# stm32_1.net
KiCad netlist of a schematic drawn in EasyEDA
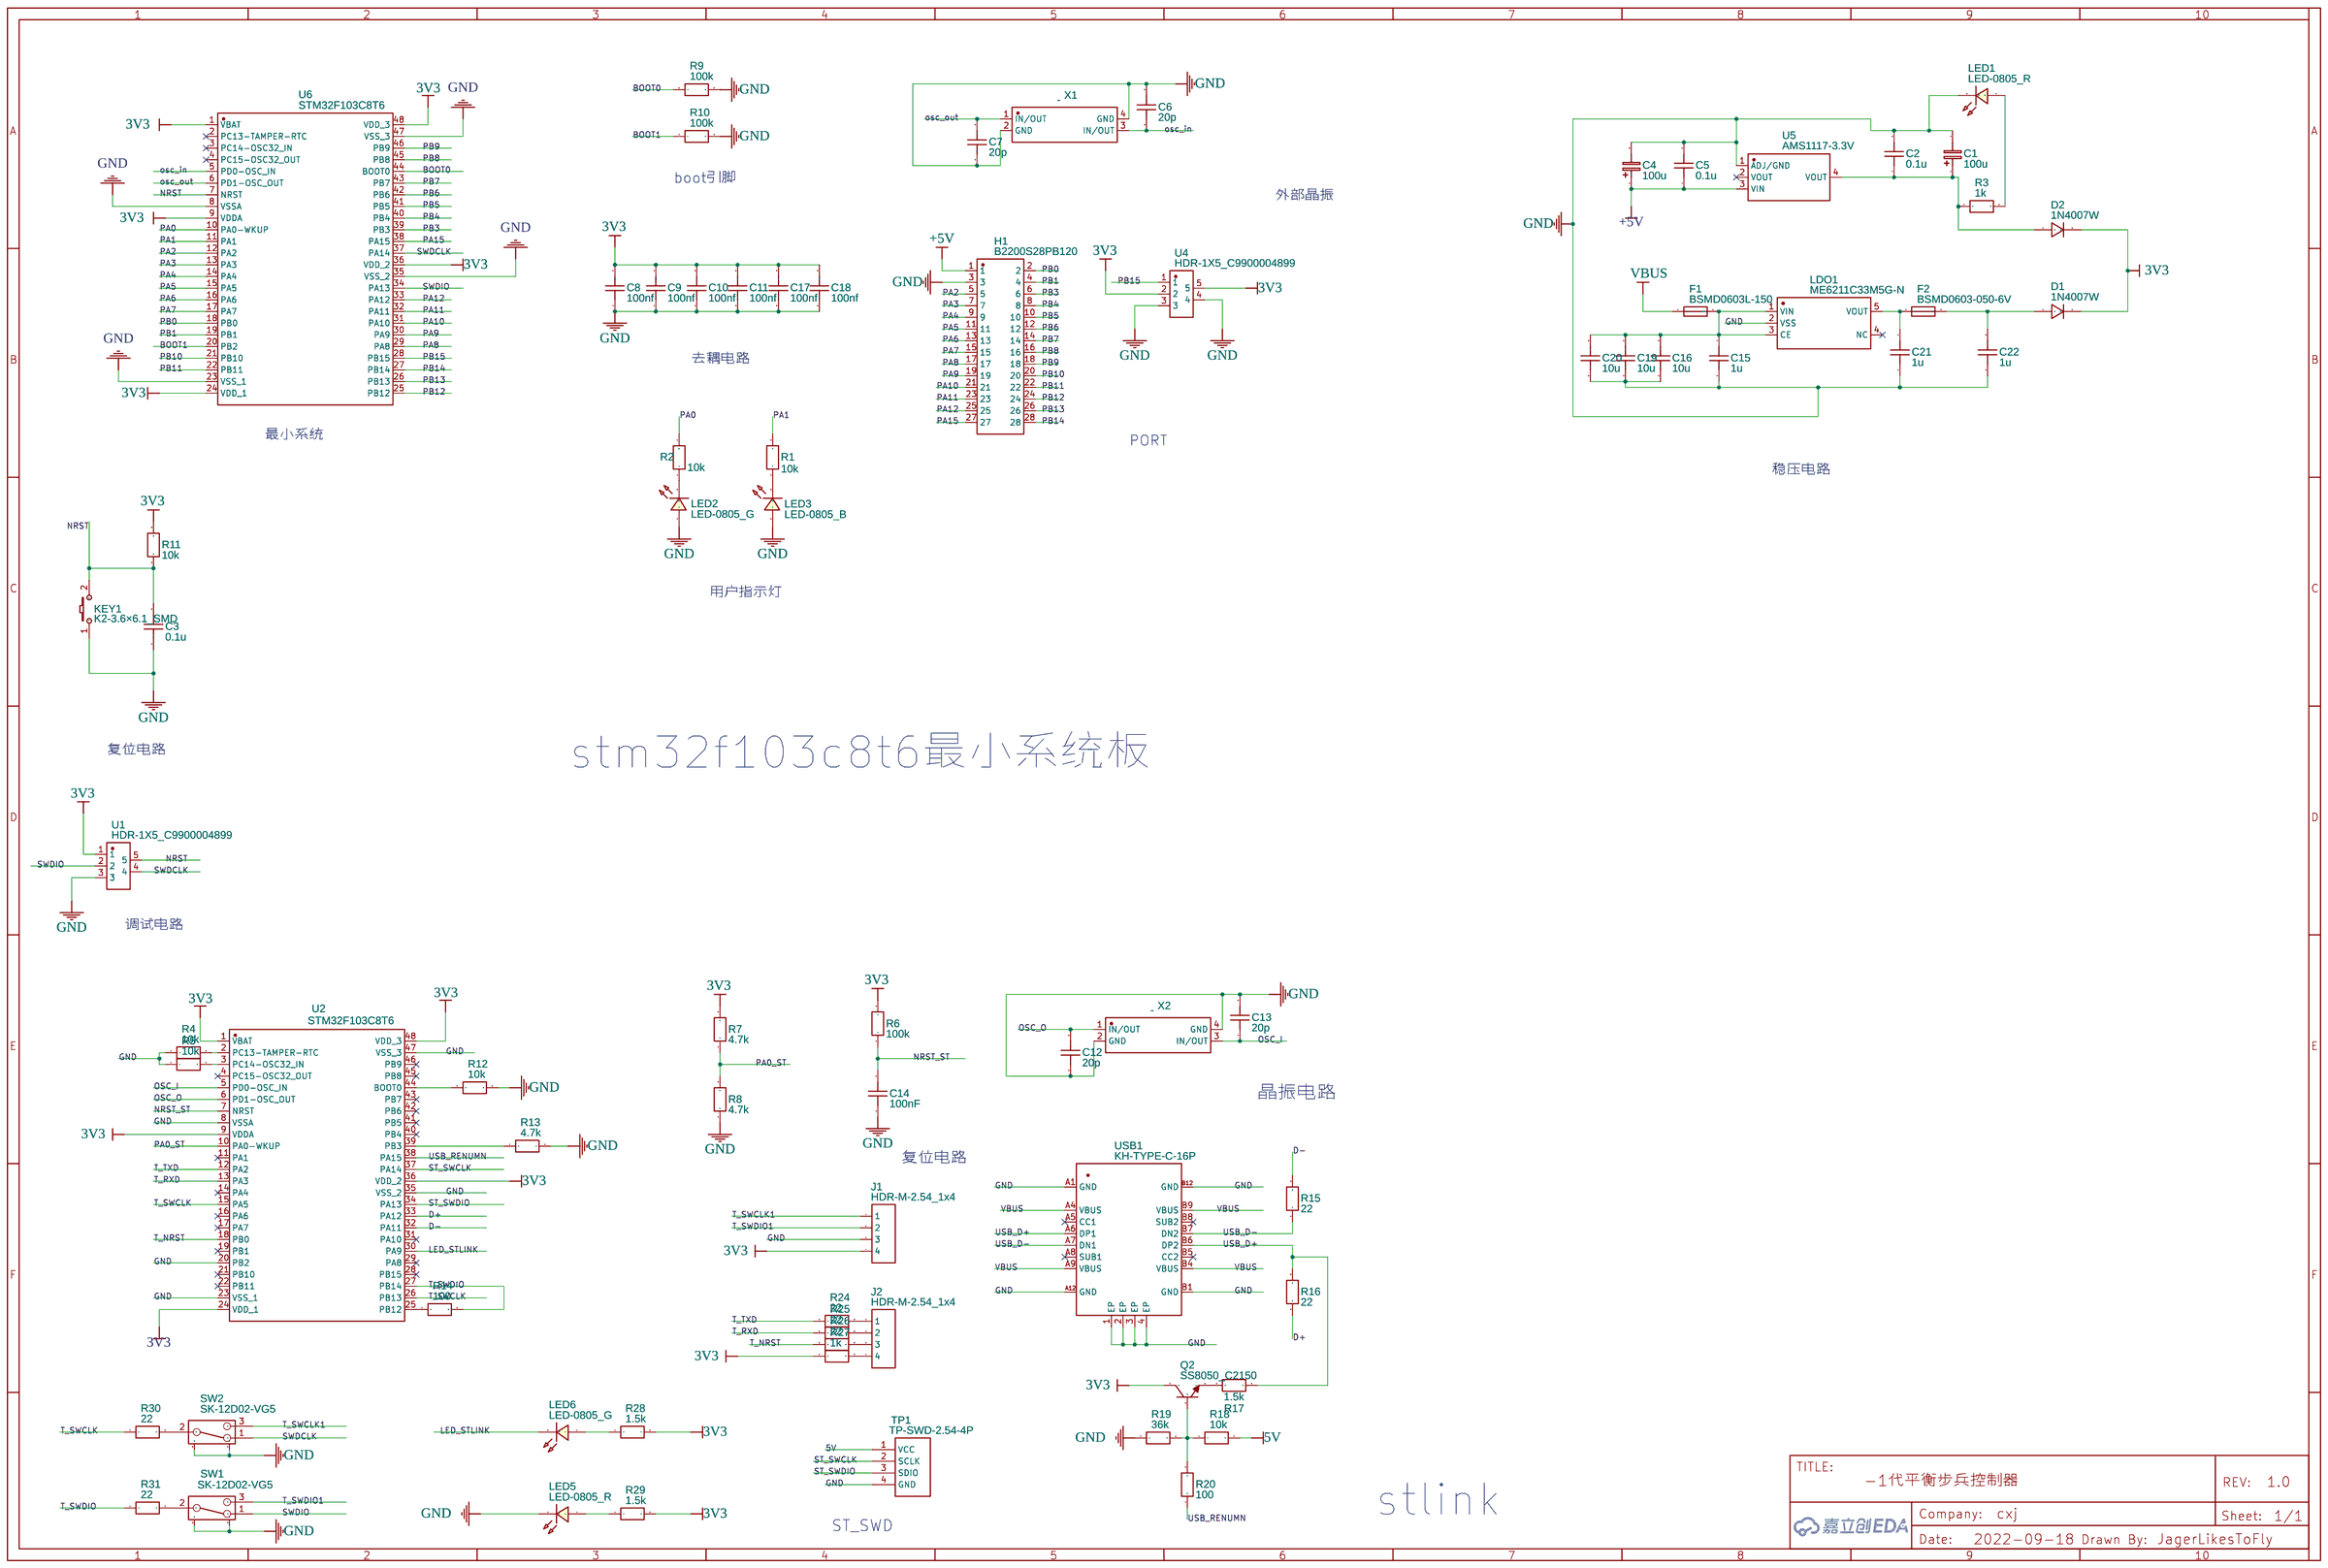
[diagram p0: schematic sheet]

(export (version "E")
  (design (tool "Eeschema 10.0.6"))
  (components
    (comp (ref "C1") (value "100u") (libsource (lib "") (part "C_Tan_SMD_A_EU")))
    (comp (ref "C2") (value "0.1u") (libsource (lib "") (part "C_0805_US")))
    (comp (ref "C3") (value "0.1u") (libsource (lib "") (part "C_0603_US")))
    (comp (ref "C4") (value "100u") (libsource (lib "") (part "C_Tan_SMD_A_EU")))
    (comp (ref "C5") (value "0.1u") (libsource (lib "") (part "C_0805_US")))
    (comp (ref "C6") (value "20p") (libsource (lib "") (part "C_0805_US")))
    (comp (ref "C7") (value "20p") (libsource (lib "") (part "C_0805_US")))
    (comp (ref "C8") (value "100nf") (libsource (lib "") (part "C_0603_US")))
    (comp (ref "C9") (value "100nf") (libsource (lib "") (part "C_0603_US")))
    (comp (ref "C10") (value "100nf") (libsource (lib "") (part "C_0603_US")))
    (comp (ref "C11") (value "100nf") (libsource (lib "") (part "C_0603_US")))
    (comp (ref "C12") (value "20p") (libsource (lib "") (part "C_0805_US")))
    (comp (ref "C13") (value "20p") (libsource (lib "") (part "C_0805_US")))
    (comp (ref "C14") (value "100nF") (libsource (lib "") (part "C_0805_US")))
    (comp (ref "C15") (value "1u") (libsource (lib "") (part "C_0805_US_1")))
    (comp (ref "C16") (value "10u") (libsource (lib "") (part "C_0805_US")))
    (comp (ref "C17") (value "100nf") (libsource (lib "") (part "C_0603_US")))
    (comp (ref "C18") (value "100nf") (libsource (lib "") (part "C_0603_US")))
    (comp (ref "C19") (value "10u") (libsource (lib "") (part "C_0805_US")))
    (comp (ref "C20") (value "10u") (libsource (lib "") (part "C_0805_US")))
    (comp (ref "C21") (value "1u") (libsource (lib "") (part "C_0805_US")))
    (comp (ref "C22") (value "1u") (libsource (lib "") (part "C_0805_US")))
    (comp (ref "D1")
      (value "1N4007W")
      (fields (field (name "BOM_Supplier Part") "C328592"))
      (libsource (lib "") (part "1N4007W"))
    )
    (comp (ref "D2")
      (value "1N4007W")
      (fields (field (name "BOM_Supplier Part") "C328592"))
      (libsource (lib "") (part "1N4007W"))
    )
    (comp (ref "F1")
      (value "BSMD0603L-150")
      (fields (field (name "BOM_Supplier Part") "C914094"))
      (libsource (lib "") (part "BSMD0603L-150"))
    )
    (comp (ref "F2")
      (value "BSMD0603-050-6V")
      (fields (field (name "BOM_Supplier Part") "C883095"))
      (libsource (lib "") (part "BSMD0603-050-6V"))
    )
    (comp (ref "H1")
      (value "B2200S28PB120")
      (fields (field (name "BOM_Supplier Part") "C379815"))
      (libsource (lib "") (part "B2200S28PB120"))
    )
    (comp (ref "J1")
      (value "HDR-M-2.54_1x4")
      (fields (field (name "BOM_Supplier Part") "C124378"))
      (libsource (lib "") (part "HDR-M-2.54_1x4"))
    )
    (comp (ref "J2")
      (value "HDR-M-2.54_1x4")
      (fields (field (name "BOM_Supplier Part") "C124378"))
      (libsource (lib "") (part "HDR-M-2.54_1x4"))
    )
    (comp (ref "KEY1")
      (value "K2-3.6×6.1_SMD")
      (fields
        (field (name "BOM_Manufacturer Part") "K2-1107ST-A4SW-06")
        (field (name "BOM_Supplier Part") "C118141")
      )
      (libsource (lib "") (part "K2-3.6×6.1_SMD"))
    )
    (comp (ref "LDO1")
      (value "ME6211C33M5G-N")
      (fields (field (name "BOM_Supplier Part") "C82942"))
      (libsource (lib "") (part "ME6211C33M5G-N"))
    )
    (comp (ref "LED1")
      (value "LED-0805_R")
      (fields
        (field (name "BOM_Manufacturer Part") "19-217/R6C-AL1M2VY/3T")
        (field (name "BOM_Supplier Part") "C72044")
      )
      (libsource (lib "") (part "LED-0603_R"))
    )
    (comp (ref "LED2")
      (value "LED-0805_G")
      (fields (field (name "BOM_Manufacturer Part") "NCD0805G1") (field (name "BOM_Supplier Part") "C84260"))
      (libsource (lib "") (part "LED-0805_G"))
    )
    (comp (ref "LED3")
      (value "LED-0805_B")
      (fields
        (field (name "BOM_Manufacturer Part") "D-B080508B1-KS2")
        (field (name "BOM_Supplier Part") "C108412")
      )
      (libsource (lib "") (part "LED-0805_B"))
    )
    (comp (ref "LED5")
      (value "LED-0805_R")
      (fields
        (field (name "BOM_Manufacturer Part") "17-21SURC/S530-A3/TR8")
        (field (name "BOM_Supplier Part") "C72037")
      )
      (libsource (lib "") (part "LED-0805_R"))
    )
    (comp (ref "LED6")
      (value "LED-0805_G")
      (fields (field (name "BOM_Manufacturer Part") "NCD0805G1") (field (name "BOM_Supplier Part") "C84260"))
      (libsource (lib "") (part "LED-0805_G_1"))
    )
    (comp (ref "Q2")
      (value "SS8050_C2150")
      (fields (field (name "BOM_Manufacturer Part") "SS8050") (field (name "BOM_Supplier Part") "C2150"))
      (libsource (lib "") (part "SS8050_C2150"))
    )
    (comp (ref "R1") (value "10k") (libsource (lib "") (part "R_0805_EU_1")))
    (comp (ref "R2") (value "10k") (libsource (lib "") (part "R_0805_EU_1")))
    (comp (ref "R3") (value "1k") (libsource (lib "") (part "R_0805_EU")))
    (comp (ref "R4") (value "10k") (libsource (lib "") (part "R_0805_EU")))
    (comp (ref "R5") (value "10k") (libsource (lib "") (part "R_0805_EU")))
    (comp (ref "R6") (value "100k") (libsource (lib "") (part "R_0805_EU_1")))
    (comp (ref "R7") (value "4.7k") (libsource (lib "") (part "R_0805_EU_1")))
    (comp (ref "R8") (value "4.7k") (libsource (lib "") (part "R_0805_EU_1")))
    (comp (ref "R9") (value "100k") (libsource (lib "") (part "R_0603_EU_1")))
    (comp (ref "R10") (value "100k") (libsource (lib "") (part "R_0603_EU_1")))
    (comp (ref "R11") (value "10k") (libsource (lib "") (part "R_0603_EU")))
    (comp (ref "R12") (value "10k") (libsource (lib "") (part "R_0805_EU")))
    (comp (ref "R13") (value "4.7k") (libsource (lib "") (part "R_0805_EU")))
    (comp (ref "R14") (value "100") (libsource (lib "") (part "R_0805_EU")))
    (comp (ref "R15") (value "22") (libsource (lib "") (part "R_0805_EU_1")))
    (comp (ref "R16") (value "22") (libsource (lib "") (part "R_0805_EU_1")))
    (comp (ref "R17") (value "1.5k") (libsource (lib "") (part "R_0805_EU")))
    (comp (ref "R18") (value "10k") (libsource (lib "") (part "R_0805_EU")))
    (comp (ref "R19") (value "36k") (libsource (lib "") (part "R_0805_EU")))
    (comp (ref "R20") (value "100") (libsource (lib "") (part "R_0805_EU_1")))
    (comp (ref "R24") (value "22") (libsource (lib "") (part "R_0805_EU")))
    (comp (ref "R25") (value "22") (libsource (lib "") (part "R_0805_EU")))
    (comp (ref "R26") (value "22") (libsource (lib "") (part "R_0805_EU")))
    (comp (ref "R27") (value "1k") (libsource (lib "") (part "R_0805_EU")))
    (comp (ref "R28") (value "1.5k") (libsource (lib "") (part "R_0805_EU")))
    (comp (ref "R29") (value "1.5k") (libsource (lib "") (part "R_0805_EU")))
    (comp (ref "R30") (value "22") (libsource (lib "") (part "R_0805_EU")))
    (comp (ref "R31") (value "22") (libsource (lib "") (part "R_0805_EU")))
    (comp (ref "SW1")
      (value "SK-12D02-VG5")
      (fields (field (name "BOM_Supplier Part") "C136722"))
      (libsource (lib "") (part "SK-12D02-VG5"))
    )
    (comp (ref "SW2")
      (value "SK-12D02-VG5")
      (fields (field (name "BOM_Supplier Part") "C136722"))
      (libsource (lib "") (part "SK-12D02-VG5"))
    )
    (comp (ref "TP1") (value "TP-SWD-2.54-4P") (libsource (lib "") (part "TP-SWD-2.54-4P")))
    (comp (ref "U1")
      (value "HDR-1X5_C9900004899")
      (fields
        (field (name "BOM_Manufacturer Part") "HDR-1X5")
        (field (name "BOM_Supplier Part") "C9900004899")
      )
      (libsource (lib "") (part "HDR-1X5_C9900004899"))
    )
    (comp (ref "U2")
      (value "STM32F103C8T6")
      (fields (field (name "BOM_Supplier Part") "C8734"))
      (libsource (lib "") (part "STM32F103C8T6"))
    )
    (comp (ref "U4")
      (value "HDR-1X5_C9900004899")
      (fields
        (field (name "BOM_Manufacturer Part") "HDR-1X5")
        (field (name "BOM_Supplier Part") "C9900004899")
      )
      (libsource (lib "") (part "HDR-1X5_C9900004899"))
    )
    (comp (ref "U5")
      (value "AMS1117-3.3V")
      (fields (field (name "BOM_Supplier Part") "C2688239"))
      (libsource (lib "") (part "AMS1117-3.3V"))
    )
    (comp (ref "U6")
      (value "STM32F103C8T6")
      (fields (field (name "BOM_Supplier Part") "C8734"))
      (libsource (lib "") (part "STM32F103C8T6"))
    )
    (comp (ref "USB1")
      (value "KH-TYPE-C-16P")
      (fields (field (name "BOM_Supplier Part") "C709357"))
      (libsource (lib "") (part "KH-TYPE-C-16P"))
    )
    (comp (ref "X1")
      (value "-")
      (fields (field (name "BOM_Manufacturer Part") "TZ1897B") (field (name "BOM_Supplier Part") "C337647"))
      (libsource (lib "") (part "TZ1897B"))
    )
    (comp (ref "X2")
      (value "-")
      (fields (field (name "BOM_Manufacturer Part") "TZ1897B") (field (name "BOM_Supplier Part") "C337647"))
      (libsource (lib "") (part "TZ1897B"))
    )
  )
  (nets
    (net (code "1") (name "+5V") (class "Default")
      (node (ref "C4") (pin "1") (pinfunction "1_1") (pintype "unspecified"))
      (node (ref "C5") (pin "1") (pinfunction "1_1") (pintype "unspecified"))
      (node (ref "H1") (pin "1") (pinfunction "1_1") (pintype "unspecified"))
      (node (ref "U5") (pin "3") (pinfunction "VIN_3") (pintype "unspecified"))
    )
    (net (code "2") (name "/BOOT0") (class "Default")
      (node (ref "R9") (pin "1") (pinfunction "1_1") (pintype "unspecified"))
      (node (ref "U6") (pin "44") (pinfunction "BOOT0_44") (pintype "unspecified"))
    )
    (net (code "3") (name "/BOOT1") (class "Default")
      (node (ref "R10") (pin "1") (pinfunction "1_1") (pintype "unspecified"))
      (node (ref "U6") (pin "20") (pinfunction "PB2_20") (pintype "unspecified"))
    )
    (net (code "4") (name "/D+") (class "Default")
      (node (ref "R16") (pin "1") (pinfunction "1_1") (pintype "unspecified"))
      (node (ref "U2") (pin "33") (pinfunction "PA12_33") (pintype "unspecified"))
    )
    (net (code "5") (name "/D-") (class "Default")
      (node (ref "R15") (pin "2") (pinfunction "2_2") (pintype "unspecified"))
      (node (ref "U2") (pin "32") (pinfunction "PA11_32") (pintype "unspecified"))
    )
    (net (code "6") (name "/LED_STLINK") (class "Default")
      (node (ref "LED6") (pin "2") (pinfunction "2_2") (pintype "unspecified"))
      (node (ref "U2") (pin "30") (pinfunction "PA9_30") (pintype "unspecified"))
    )
    (net (code "7") (name "/NRST") (class "Default")
      (node (ref "C3") (pin "2") (pinfunction "2_2") (pintype "unspecified"))
      (node (ref "KEY1") (pin "2") (pinfunction "2_2") (pintype "unspecified"))
      (node (ref "R11") (pin "1") (pinfunction "1_1") (pintype "unspecified"))
      (node (ref "U1") (pin "5") (pinfunction "5_5") (pintype "unspecified"))
      (node (ref "U6") (pin "7") (pinfunction "NRST_7") (pintype "unspecified"))
    )
    (net (code "8") (name "/NRST_ST") (class "Default")
      (node (ref "C14") (pin "2") (pinfunction "2_2") (pintype "unspecified"))
      (node (ref "R6") (pin "1") (pinfunction "1_1") (pintype "unspecified"))
      (node (ref "U2") (pin "7") (pinfunction "NRST_7") (pintype "unspecified"))
    )
    (net (code "9") (name "/OSC_I") (class "Default")
      (node (ref "C13") (pin "1") (pinfunction "1_1") (pintype "unspecified"))
      (node (ref "U2") (pin "5") (pinfunction "PD0-OSC_IN_5") (pintype "unspecified"))
      (node (ref "X2") (pin "3") (pinfunction "IN/OUT_3") (pintype "unspecified"))
    )
    (net (code "10") (name "/OSC_O") (class "Default")
      (node (ref "C12") (pin "2") (pinfunction "2_2") (pintype "unspecified"))
      (node (ref "U2") (pin "6") (pinfunction "PD1-OSC_OUT_6") (pintype "unspecified"))
      (node (ref "X2") (pin "1") (pinfunction "IN/OUT_1") (pintype "unspecified"))
    )
    (net (code "11") (name "/PA0") (class "Default")
      (node (ref "R2") (pin "2") (pinfunction "2_2") (pintype "unspecified"))
      (node (ref "U6") (pin "10") (pinfunction "PA0-WKUP_10") (pintype "unspecified"))
    )
    (net (code "12") (name "/PA0_ST") (class "Default")
      (node (ref "R7") (pin "1") (pinfunction "1_1") (pintype "unspecified"))
      (node (ref "R8") (pin "2") (pinfunction "2_2") (pintype "unspecified"))
      (node (ref "U2") (pin "10") (pinfunction "PA0-WKUP_10") (pintype "unspecified"))
    )
    (net (code "13") (name "/PA1") (class "Default")
      (node (ref "R1") (pin "2") (pinfunction "2_2") (pintype "unspecified"))
      (node (ref "U6") (pin "11") (pinfunction "PA1_11") (pintype "unspecified"))
    )
    (net (code "14") (name "/PA2") (class "Default")
      (node (ref "H1") (pin "5") (pinfunction "5_5") (pintype "unspecified"))
      (node (ref "U6") (pin "12") (pinfunction "PA2_12") (pintype "unspecified"))
    )
    (net (code "15") (name "/PA3") (class "Default")
      (node (ref "H1") (pin "7") (pinfunction "7_7") (pintype "unspecified"))
      (node (ref "U6") (pin "13") (pinfunction "PA3_13") (pintype "unspecified"))
    )
    (net (code "16") (name "/PA4") (class "Default")
      (node (ref "H1") (pin "9") (pinfunction "9_9") (pintype "unspecified"))
      (node (ref "U6") (pin "14") (pinfunction "PA4_14") (pintype "unspecified"))
    )
    (net (code "17") (name "/PA5") (class "Default")
      (node (ref "H1") (pin "11") (pinfunction "11_11") (pintype "unspecified"))
      (node (ref "U6") (pin "15") (pinfunction "PA5_15") (pintype "unspecified"))
    )
    (net (code "18") (name "/PA6") (class "Default")
      (node (ref "H1") (pin "13") (pinfunction "13_13") (pintype "unspecified"))
      (node (ref "U6") (pin "16") (pinfunction "PA6_16") (pintype "unspecified"))
    )
    (net (code "19") (name "/PA7") (class "Default")
      (node (ref "H1") (pin "15") (pinfunction "15_15") (pintype "unspecified"))
      (node (ref "U6") (pin "17") (pinfunction "PA7_17") (pintype "unspecified"))
    )
    (net (code "20") (name "/PA8") (class "Default")
      (node (ref "H1") (pin "17") (pinfunction "17_17") (pintype "unspecified"))
      (node (ref "U6") (pin "29") (pinfunction "PA8_29") (pintype "unspecified"))
    )
    (net (code "21") (name "/PA9") (class "Default")
      (node (ref "H1") (pin "19") (pinfunction "19_19") (pintype "unspecified"))
      (node (ref "U6") (pin "30") (pinfunction "PA9_30") (pintype "unspecified"))
    )
    (net (code "22") (name "/PA10") (class "Default")
      (node (ref "H1") (pin "21") (pinfunction "21_21") (pintype "unspecified"))
      (node (ref "U6") (pin "31") (pinfunction "PA10_31") (pintype "unspecified"))
    )
    (net (code "23") (name "/PA11") (class "Default")
      (node (ref "H1") (pin "23") (pinfunction "23_23") (pintype "unspecified"))
      (node (ref "U6") (pin "32") (pinfunction "PA11_32") (pintype "unspecified"))
    )
    (net (code "24") (name "/PA12") (class "Default")
      (node (ref "H1") (pin "25") (pinfunction "25_25") (pintype "unspecified"))
      (node (ref "U6") (pin "33") (pinfunction "PA12_33") (pintype "unspecified"))
    )
    (net (code "25") (name "/PA15") (class "Default")
      (node (ref "H1") (pin "27") (pinfunction "27_27") (pintype "unspecified"))
      (node (ref "U6") (pin "38") (pinfunction "PA15_38") (pintype "unspecified"))
    )
    (net (code "26") (name "/PB0") (class "Default")
      (node (ref "H1") (pin "2") (pinfunction "2_2") (pintype "unspecified"))
      (node (ref "U6") (pin "18") (pinfunction "PB0_18") (pintype "unspecified"))
    )
    (net (code "27") (name "/PB1") (class "Default")
      (node (ref "H1") (pin "4") (pinfunction "4_4") (pintype "unspecified"))
      (node (ref "U6") (pin "19") (pinfunction "PB1_19") (pintype "unspecified"))
    )
    (net (code "28") (name "/PB3") (class "Default")
      (node (ref "H1") (pin "6") (pinfunction "6_6") (pintype "unspecified"))
      (node (ref "U6") (pin "39") (pinfunction "PB3_39") (pintype "unspecified"))
    )
    (net (code "29") (name "/PB4") (class "Default")
      (node (ref "H1") (pin "8") (pinfunction "8_8") (pintype "unspecified"))
      (node (ref "U6") (pin "40") (pinfunction "PB4_40") (pintype "unspecified"))
    )
    (net (code "30") (name "/PB5") (class "Default")
      (node (ref "H1") (pin "10") (pinfunction "10_10") (pintype "unspecified"))
      (node (ref "U6") (pin "41") (pinfunction "PB5_41") (pintype "unspecified"))
    )
    (net (code "31") (name "/PB6") (class "Default")
      (node (ref "H1") (pin "12") (pinfunction "12_12") (pintype "unspecified"))
      (node (ref "U6") (pin "42") (pinfunction "PB6_42") (pintype "unspecified"))
    )
    (net (code "32") (name "/PB7") (class "Default")
      (node (ref "H1") (pin "14") (pinfunction "14_14") (pintype "unspecified"))
      (node (ref "U6") (pin "43") (pinfunction "PB7_43") (pintype "unspecified"))
    )
    (net (code "33") (name "/PB8") (class "Default")
      (node (ref "H1") (pin "16") (pinfunction "16_16") (pintype "unspecified"))
      (node (ref "U6") (pin "45") (pinfunction "PB8_45") (pintype "unspecified"))
    )
    (net (code "34") (name "/PB9") (class "Default")
      (node (ref "H1") (pin "18") (pinfunction "18_18") (pintype "unspecified"))
      (node (ref "U6") (pin "46") (pinfunction "PB9_46") (pintype "unspecified"))
    )
    (net (code "35") (name "/PB10") (class "Default")
      (node (ref "H1") (pin "20") (pinfunction "20_20") (pintype "unspecified"))
      (node (ref "U6") (pin "21") (pinfunction "PB10_21") (pintype "unspecified"))
    )
    (net (code "36") (name "/PB11") (class "Default")
      (node (ref "H1") (pin "22") (pinfunction "22_22") (pintype "unspecified"))
      (node (ref "U6") (pin "22") (pinfunction "PB11_22") (pintype "unspecified"))
    )
    (net (code "37") (name "/PB12") (class "Default")
      (node (ref "H1") (pin "24") (pinfunction "24_24") (pintype "unspecified"))
      (node (ref "U6") (pin "25") (pinfunction "PB12_25") (pintype "unspecified"))
    )
    (net (code "38") (name "/PB13") (class "Default")
      (node (ref "H1") (pin "26") (pinfunction "26_26") (pintype "unspecified"))
      (node (ref "U6") (pin "26") (pinfunction "PB13_26") (pintype "unspecified"))
    )
    (net (code "39") (name "/PB14") (class "Default")
      (node (ref "H1") (pin "28") (pinfunction "28_28") (pintype "unspecified"))
      (node (ref "U6") (pin "27") (pinfunction "PB14_27") (pintype "unspecified"))
    )
    (net (code "40") (name "/PB15") (class "Default")
      (node (ref "U4") (pin "1") (pinfunction "1_1") (pintype "unspecified"))
      (node (ref "U6") (pin "28") (pinfunction "PB15_28") (pintype "unspecified"))
    )
    (net (code "41") (name "/ST_SWCLK") (class "Default")
      (node (ref "TP1") (pin "2") (pinfunction "SCLK_2") (pintype "unspecified"))
      (node (ref "U2") (pin "37") (pinfunction "PA14_37") (pintype "unspecified"))
    )
    (net (code "42") (name "/ST_SWDIO") (class "Default")
      (node (ref "TP1") (pin "3") (pinfunction "SDIO_3") (pintype "unspecified"))
      (node (ref "U2") (pin "34") (pinfunction "PA13_34") (pintype "unspecified"))
    )
    (net (code "43") (name "/SWDCLK") (class "Default")
      (node (ref "SW2") (pin "1") (pinfunction "1_1") (pintype "unspecified"))
      (node (ref "U1") (pin "4") (pinfunction "4_4") (pintype "unspecified"))
      (node (ref "U6") (pin "37") (pinfunction "PA14_37") (pintype "unspecified"))
    )
    (net (code "44") (name "/SWDIO") (class "Default")
      (node (ref "SW1") (pin "1") (pinfunction "1_1") (pintype "unspecified"))
      (node (ref "U1") (pin "2") (pinfunction "2_2") (pintype "unspecified"))
      (node (ref "U6") (pin "34") (pinfunction "PA13_34") (pintype "unspecified"))
    )
    (net (code "45") (name "/T_NRST") (class "Default")
      (node (ref "R26") (pin "1") (pinfunction "1_1") (pintype "unspecified"))
      (node (ref "U2") (pin "18") (pinfunction "PB0_18") (pintype "unspecified"))
    )
    (net (code "46") (name "/T_RXD") (class "Default")
      (node (ref "R25") (pin "1") (pinfunction "1_1") (pintype "unspecified"))
      (node (ref "U2") (pin "13") (pinfunction "PA3_13") (pintype "unspecified"))
    )
    (net (code "47") (name "/T_SWCLK") (class "Default")
      (node (ref "R30") (pin "1") (pinfunction "1_1") (pintype "unspecified"))
      (node (ref "U2") (pin "15") (pinfunction "PA5_15") (pintype "unspecified"))
      (node (ref "U2") (pin "26") (pinfunction "PB13_26") (pintype "unspecified"))
    )
    (net (code "48") (name "/T_SWCLK1") (class "Default")
      (node (ref "J1") (pin "1") (pinfunction "1_1") (pintype "unspecified"))
      (node (ref "SW2") (pin "3") (pinfunction "3_3") (pintype "unspecified"))
    )
    (net (code "49") (name "/T_SWDIO") (class "Default")
      (node (ref "R14") (pin "2") (pinfunction "2_2") (pintype "unspecified"))
      (node (ref "R31") (pin "1") (pinfunction "1_1") (pintype "unspecified"))
      (node (ref "U2") (pin "27") (pinfunction "PB14_27") (pintype "unspecified"))
    )
    (net (code "50") (name "/T_SWDIO1") (class "Default")
      (node (ref "J1") (pin "2") (pinfunction "2_2") (pintype "unspecified"))
      (node (ref "SW1") (pin "3") (pinfunction "3_3") (pintype "unspecified"))
    )
    (net (code "51") (name "/T_TXD") (class "Default")
      (node (ref "R24") (pin "1") (pinfunction "1_1") (pintype "unspecified"))
      (node (ref "U2") (pin "12") (pinfunction "PA2_12") (pintype "unspecified"))
    )
    (net (code "52") (name "/USB_D+") (class "Default")
      (node (ref "R16") (pin "2") (pinfunction "2_2") (pintype "unspecified"))
      (node (ref "R17") (pin "2") (pinfunction "2_2") (pintype "unspecified"))
      (node (ref "USB1") (pin "A6") (pinfunction "DP1_A6") (pintype "unspecified"))
      (node (ref "USB1") (pin "B6") (pinfunction "DP2_B6") (pintype "unspecified"))
    )
    (net (code "53") (name "/USB_D-") (class "Default")
      (node (ref "R15") (pin "1") (pinfunction "1_1") (pintype "unspecified"))
      (node (ref "USB1") (pin "A7") (pinfunction "DN1_A7") (pintype "unspecified"))
      (node (ref "USB1") (pin "B7") (pinfunction "DN2_B7") (pintype "unspecified"))
    )
    (net (code "54") (name "/USB_RENUMN") (class "Default")
      (node (ref "R20") (pin "1") (pinfunction "1_1") (pintype "unspecified"))
      (node (ref "U2") (pin "38") (pinfunction "PA15_38") (pintype "unspecified"))
    )
    (net (code "55") (name "/osc_in") (class "Default")
      (node (ref "C6") (pin "1") (pinfunction "1_1") (pintype "unspecified"))
      (node (ref "U6") (pin "5") (pinfunction "PD0-OSC_IN_5") (pintype "unspecified"))
      (node (ref "X1") (pin "3") (pinfunction "IN/OUT_3") (pintype "unspecified"))
    )
    (net (code "56") (name "/osc_out") (class "Default")
      (node (ref "C7") (pin "2") (pinfunction "2_2") (pintype "unspecified"))
      (node (ref "U6") (pin "6") (pinfunction "PD1-OSC_OUT_6") (pintype "unspecified"))
      (node (ref "X1") (pin "1") (pinfunction "IN/OUT_1") (pintype "unspecified"))
    )
    (net (code "57") (name "3V3") (class "Default")
      (node (ref "C10") (pin "2") (pinfunction "2_2") (pintype "unspecified"))
      (node (ref "C11") (pin "2") (pinfunction "2_2") (pintype "unspecified"))
      (node (ref "C17") (pin "2") (pinfunction "2_2") (pintype "unspecified"))
      (node (ref "C18") (pin "2") (pinfunction "2_2") (pintype "unspecified"))
      (node (ref "C8") (pin "2") (pinfunction "2_2") (pintype "unspecified"))
      (node (ref "C9") (pin "2") (pinfunction "2_2") (pintype "unspecified"))
      (node (ref "D1") (pin "1") (pinfunction "1_1") (pintype "unspecified"))
      (node (ref "D2") (pin "1") (pinfunction "1_1") (pintype "unspecified"))
      (node (ref "J1") (pin "4") (pinfunction "4_4") (pintype "unspecified"))
      (node (ref "Q2") (pin "3") (pinfunction "C_3") (pintype "unspecified"))
      (node (ref "R11") (pin "2") (pinfunction "2_2") (pintype "unspecified"))
      (node (ref "R27") (pin "1") (pinfunction "1_1") (pintype "unspecified"))
      (node (ref "R28") (pin "2") (pinfunction "2_2") (pintype "unspecified"))
      (node (ref "R29") (pin "2") (pinfunction "2_2") (pintype "unspecified"))
      (node (ref "R6") (pin "2") (pinfunction "2_2") (pintype "unspecified"))
      (node (ref "R7") (pin "2") (pinfunction "2_2") (pintype "unspecified"))
      (node (ref "U1") (pin "1") (pinfunction "1_1") (pintype "unspecified"))
      (node (ref "U2") (pin "1") (pinfunction "VBAT_1") (pintype "unspecified"))
      (node (ref "U2") (pin "24") (pinfunction "VDD_1_24") (pintype "unspecified"))
      (node (ref "U2") (pin "36") (pinfunction "VDD_2_36") (pintype "unspecified"))
      (node (ref "U2") (pin "48") (pinfunction "VDD_3_48") (pintype "unspecified"))
      (node (ref "U2") (pin "9") (pinfunction "VDDA_9") (pintype "unspecified"))
      (node (ref "U4") (pin "2") (pinfunction "2_2") (pintype "unspecified"))
      (node (ref "U4") (pin "5") (pinfunction "5_5") (pintype "unspecified"))
      (node (ref "U6") (pin "1") (pinfunction "VBAT_1") (pintype "unspecified"))
      (node (ref "U6") (pin "24") (pinfunction "VDD_1_24") (pintype "unspecified"))
      (node (ref "U6") (pin "36") (pinfunction "VDD_2_36") (pintype "unspecified"))
      (node (ref "U6") (pin "48") (pinfunction "VDD_3_48") (pintype "unspecified"))
      (node (ref "U6") (pin "9") (pinfunction "VDDA_9") (pintype "unspecified"))
    )
    (net (code "58") (name "5V") (class "Default")
      (node (ref "R18") (pin "2") (pinfunction "2_2") (pintype "unspecified"))
      (node (ref "TP1") (pin "1") (pinfunction "VCC_1") (pintype "unspecified"))
    )
    (net (code "59") (name "GND") (class "Default")
      (node (ref "C1") (pin "2") (pinfunction "2_2") (pintype "unspecified"))
      (node (ref "C10") (pin "1") (pinfunction "1_1") (pintype "unspecified"))
      (node (ref "C11") (pin "1") (pinfunction "1_1") (pintype "unspecified"))
      (node (ref "C12") (pin "1") (pinfunction "1_1") (pintype "unspecified"))
      (node (ref "C13") (pin "2") (pinfunction "2_2") (pintype "unspecified"))
      (node (ref "C14") (pin "1") (pinfunction "1_1") (pintype "unspecified"))
      (node (ref "C15") (pin "2") (pinfunction "2_2") (pintype "unspecified"))
      (node (ref "C16") (pin "1") (pinfunction "1_1") (pintype "unspecified"))
      (node (ref "C17") (pin "1") (pinfunction "1_1") (pintype "unspecified"))
      (node (ref "C18") (pin "1") (pinfunction "1_1") (pintype "unspecified"))
      (node (ref "C19") (pin "1") (pinfunction "1_1") (pintype "unspecified"))
      (node (ref "C2") (pin "2") (pinfunction "2_2") (pintype "unspecified"))
      (node (ref "C20") (pin "1") (pinfunction "1_1") (pintype "unspecified"))
      (node (ref "C21") (pin "1") (pinfunction "1_1") (pintype "unspecified"))
      (node (ref "C22") (pin "1") (pinfunction "1_1") (pintype "unspecified"))
      (node (ref "C3") (pin "1") (pinfunction "1_1") (pintype "unspecified"))
      (node (ref "C4") (pin "2") (pinfunction "2_2") (pintype "unspecified"))
      (node (ref "C5") (pin "2") (pinfunction "2_2") (pintype "unspecified"))
      (node (ref "C6") (pin "2") (pinfunction "2_2") (pintype "unspecified"))
      (node (ref "C7") (pin "1") (pinfunction "1_1") (pintype "unspecified"))
      (node (ref "C8") (pin "1") (pinfunction "1_1") (pintype "unspecified"))
      (node (ref "C9") (pin "1") (pinfunction "1_1") (pintype "unspecified"))
      (node (ref "H1") (pin "3") (pinfunction "3_3") (pintype "unspecified"))
      (node (ref "J1") (pin "3") (pinfunction "3_3") (pintype "unspecified"))
      (node (ref "KEY1") (pin "1") (pinfunction "1_1") (pintype "unspecified"))
      (node (ref "LDO1") (pin "2") (pinfunction "VSS_2") (pintype "unspecified"))
      (node (ref "LED1") (pin "2") (pinfunction "2_2") (pintype "unspecified"))
      (node (ref "LED2") (pin "1") (pinfunction "1_1") (pintype "unspecified"))
      (node (ref "LED3") (pin "1") (pinfunction "1_1") (pintype "unspecified"))
      (node (ref "LED5") (pin "2") (pinfunction "2_2") (pintype "unspecified"))
      (node (ref "R10") (pin "2") (pinfunction "2_2") (pintype "unspecified"))
      (node (ref "R12") (pin "2") (pinfunction "2_2") (pintype "unspecified"))
      (node (ref "R13") (pin "2") (pinfunction "2_2") (pintype "unspecified"))
      (node (ref "R19") (pin "1") (pinfunction "1_1") (pintype "unspecified"))
      (node (ref "R4") (pin "1") (pinfunction "1_1") (pintype "unspecified"))
      (node (ref "R5") (pin "1") (pinfunction "1_1") (pintype "unspecified"))
      (node (ref "R8") (pin "1") (pinfunction "1_1") (pintype "unspecified"))
      (node (ref "R9") (pin "2") (pinfunction "2_2") (pintype "unspecified"))
      (node (ref "SW1") (pin "4") (pinfunction "4_4") (pintype "unspecified"))
      (node (ref "SW1") (pin "5") (pinfunction "5_5") (pintype "unspecified"))
      (node (ref "SW2") (pin "4") (pinfunction "4_4") (pintype "unspecified"))
      (node (ref "SW2") (pin "5") (pinfunction "5_5") (pintype "unspecified"))
      (node (ref "TP1") (pin "4") (pinfunction "GND_4") (pintype "unspecified"))
      (node (ref "U1") (pin "3") (pinfunction "3_3") (pintype "unspecified"))
      (node (ref "U2") (pin "20") (pinfunction "PB2_20") (pintype "unspecified"))
      (node (ref "U2") (pin "23") (pinfunction "VSS_1_23") (pintype "unspecified"))
      (node (ref "U2") (pin "35") (pinfunction "VSS_2_35") (pintype "unspecified"))
      (node (ref "U2") (pin "47") (pinfunction "VSS_3_47") (pintype "unspecified"))
      (node (ref "U2") (pin "8") (pinfunction "VSSA_8") (pintype "unspecified"))
      (node (ref "U4") (pin "3") (pinfunction "3_3") (pintype "unspecified"))
      (node (ref "U4") (pin "4") (pinfunction "4_4") (pintype "unspecified"))
      (node (ref "U5") (pin "1") (pinfunction "ADJ/GND_1") (pintype "unspecified"))
      (node (ref "U6") (pin "23") (pinfunction "VSS_1_23") (pintype "unspecified"))
      (node (ref "U6") (pin "35") (pinfunction "VSS_2_35") (pintype "unspecified"))
      (node (ref "U6") (pin "47") (pinfunction "VSS_3_47") (pintype "unspecified"))
      (node (ref "U6") (pin "8") (pinfunction "VSSA_8") (pintype "unspecified"))
      (node (ref "USB1") (pin "1") (pinfunction "EP_1") (pintype "unspecified"))
      (node (ref "USB1") (pin "2") (pinfunction "EP_2") (pintype "unspecified"))
      (node (ref "USB1") (pin "3") (pinfunction "EP_3") (pintype "unspecified"))
      (node (ref "USB1") (pin "4") (pinfunction "EP_4") (pintype "unspecified"))
      (node (ref "USB1") (pin "A1") (pinfunction "GND_A1") (pintype "unspecified"))
      (node (ref "USB1") (pin "A12") (pinfunction "GND_A12") (pintype "unspecified"))
      (node (ref "USB1") (pin "B1") (pinfunction "GND_B1") (pintype "unspecified"))
      (node (ref "USB1") (pin "B12") (pinfunction "GND_B12") (pintype "unspecified"))
      (node (ref "X1") (pin "2") (pinfunction "GND_2") (pintype "unspecified"))
      (node (ref "X1") (pin "4") (pinfunction "GND_4") (pintype "unspecified"))
      (node (ref "X2") (pin "2") (pinfunction "GND_2") (pintype "unspecified"))
      (node (ref "X2") (pin "4") (pinfunction "GND_4") (pintype "unspecified"))
    )
    (net (code "60") (name "Net-(C1-Pad1)") (class "Default")
      (node (ref "C1") (pin "1") (pinfunction "1_1") (pintype "unspecified"))
      (node (ref "C2") (pin "1") (pinfunction "1_1") (pintype "unspecified"))
      (node (ref "D2") (pin "2") (pinfunction "2_2") (pintype "unspecified"))
      (node (ref "R3") (pin "1") (pinfunction "1_1") (pintype "unspecified"))
      (node (ref "U5") (pin "4") (pinfunction "VOUT_4") (pintype "unspecified"))
    )
    (net (code "61") (name "Net-(C22-Pad2)") (class "Default")
      (node (ref "C22") (pin "2") (pinfunction "2_2") (pintype "unspecified"))
      (node (ref "D1") (pin "2") (pinfunction "2_2") (pintype "unspecified"))
      (node (ref "F2") (pin "2") (pinfunction "2_2") (pintype "unspecified"))
    )
    (net (code "62") (name "Net-(J2-Pad1)") (class "Default")
      (node (ref "J2") (pin "1") (pinfunction "1_1") (pintype "unspecified"))
      (node (ref "R24") (pin "2") (pinfunction "2_2") (pintype "unspecified"))
    )
    (net (code "63") (name "Net-(J2-Pad2)") (class "Default")
      (node (ref "J2") (pin "2") (pinfunction "2_2") (pintype "unspecified"))
      (node (ref "R25") (pin "2") (pinfunction "2_2") (pintype "unspecified"))
    )
    (net (code "64") (name "Net-(J2-Pad3)") (class "Default")
      (node (ref "J2") (pin "3") (pinfunction "3_3") (pintype "unspecified"))
      (node (ref "R26") (pin "2") (pinfunction "2_2") (pintype "unspecified"))
    )
    (net (code "65") (name "Net-(J2-Pad4)") (class "Default")
      (node (ref "J2") (pin "4") (pinfunction "4_4") (pintype "unspecified"))
      (node (ref "R27") (pin "2") (pinfunction "2_2") (pintype "unspecified"))
    )
    (net (code "66") (name "Net-(LDO1-CE)") (class "Default")
      (node (ref "C15") (pin "1") (pinfunction "1_1") (pintype "unspecified"))
      (node (ref "C16") (pin "2") (pinfunction "2_2") (pintype "unspecified"))
      (node (ref "C19") (pin "2") (pinfunction "2_2") (pintype "unspecified"))
      (node (ref "C20") (pin "2") (pinfunction "2_2") (pintype "unspecified"))
      (node (ref "F1") (pin "2") (pinfunction "2_2") (pintype "unspecified"))
      (node (ref "LDO1") (pin "1") (pinfunction "VIN_1") (pintype "unspecified"))
      (node (ref "LDO1") (pin "3") (pinfunction "CE_3") (pintype "unspecified"))
    )
    (net (code "67") (name "Net-(LDO1-VOUT)") (class "Default")
      (node (ref "C21") (pin "2") (pinfunction "2_2") (pintype "unspecified"))
      (node (ref "F2") (pin "1") (pinfunction "1_1") (pintype "unspecified"))
      (node (ref "LDO1") (pin "5") (pinfunction "VOUT_5") (pintype "unspecified"))
    )
    (net (code "68") (name "Net-(LED1-Pad1)") (class "Default")
      (node (ref "LED1") (pin "1") (pinfunction "1_1") (pintype "unspecified"))
      (node (ref "R3") (pin "2") (pinfunction "2_2") (pintype "unspecified"))
    )
    (net (code "69") (name "Net-(LED2-Pad2)") (class "Default")
      (node (ref "LED2") (pin "2") (pinfunction "2_2") (pintype "unspecified"))
      (node (ref "R2") (pin "1") (pinfunction "1_1") (pintype "unspecified"))
    )
    (net (code "70") (name "Net-(LED3-Pad2)") (class "Default")
      (node (ref "LED3") (pin "2") (pinfunction "2_2") (pintype "unspecified"))
      (node (ref "R1") (pin "1") (pinfunction "1_1") (pintype "unspecified"))
    )
    (net (code "71") (name "Net-(LED5-Pad1)") (class "Default")
      (node (ref "LED5") (pin "1") (pinfunction "1_1") (pintype "unspecified"))
      (node (ref "R29") (pin "1") (pinfunction "1_1") (pintype "unspecified"))
    )
    (net (code "72") (name "Net-(LED6-Pad1)") (class "Default")
      (node (ref "LED6") (pin "1") (pinfunction "1_1") (pintype "unspecified"))
      (node (ref "R28") (pin "1") (pinfunction "1_1") (pintype "unspecified"))
    )
    (net (code "73") (name "Net-(Q2-B)") (class "Default")
      (node (ref "Q2") (pin "1") (pinfunction "B_1") (pintype "unspecified"))
      (node (ref "R18") (pin "1") (pinfunction "1_1") (pintype "unspecified"))
      (node (ref "R19") (pin "2") (pinfunction "2_2") (pintype "unspecified"))
      (node (ref "R20") (pin "2") (pinfunction "2_2") (pintype "unspecified"))
    )
    (net (code "74") (name "Net-(Q2-E)") (class "Default")
      (node (ref "Q2") (pin "2") (pinfunction "E_2") (pintype "unspecified"))
      (node (ref "R17") (pin "1") (pinfunction "1_1") (pintype "unspecified"))
    )
    (net (code "75") (name "Net-(R30-Pad2)") (class "Default")
      (node (ref "R30") (pin "2") (pinfunction "2_2") (pintype "unspecified"))
      (node (ref "SW2") (pin "2") (pinfunction "2_2") (pintype "unspecified"))
    )
    (net (code "76") (name "Net-(R31-Pad2)") (class "Default")
      (node (ref "R31") (pin "2") (pinfunction "2_2") (pintype "unspecified"))
      (node (ref "SW1") (pin "2") (pinfunction "2_2") (pintype "unspecified"))
    )
    (net (code "77") (name "Net-(U2-BOOT0)") (class "Default")
      (node (ref "R12") (pin "1") (pinfunction "1_1") (pintype "unspecified"))
      (node (ref "U2") (pin "44") (pinfunction "BOOT0_44") (pintype "unspecified"))
    )
    (net (code "78") (name "Net-(U2-PB3)") (class "Default")
      (node (ref "R13") (pin "1") (pinfunction "1_1") (pintype "unspecified"))
      (node (ref "U2") (pin "39") (pinfunction "PB3_39") (pintype "unspecified"))
    )
    (net (code "79") (name "Net-(U2-PB12)") (class "Default")
      (node (ref "R14") (pin "1") (pinfunction "1_1") (pintype "unspecified"))
      (node (ref "U2") (pin "25") (pinfunction "PB12_25") (pintype "unspecified"))
    )
    (net (code "80") (name "Net-(U2-PC13-TAMPER-RTC)") (class "Default")
      (node (ref "R4") (pin "2") (pinfunction "2_2") (pintype "unspecified"))
      (node (ref "U2") (pin "2") (pinfunction "PC13-TAMPER-RTC_2") (pintype "unspecified"))
    )
    (net (code "81") (name "Net-(U2-PC14-OSC32_IN)") (class "Default")
      (node (ref "R5") (pin "2") (pinfunction "2_2") (pintype "unspecified"))
      (node (ref "U2") (pin "3") (pinfunction "PC14-OSC32_IN_3") (pintype "unspecified"))
    )
    (net (code "82") (name "VBUS") (class "Default")
      (node (ref "F1") (pin "1") (pinfunction "1_1") (pintype "unspecified"))
      (node (ref "USB1") (pin "A4") (pinfunction "VBUS_A4") (pintype "unspecified"))
      (node (ref "USB1") (pin "A9") (pinfunction "VBUS_A9") (pintype "unspecified"))
      (node (ref "USB1") (pin "B4") (pinfunction "VBUS_B4") (pintype "unspecified"))
      (node (ref "USB1") (pin "B9") (pinfunction "VBUS_B9") (pintype "unspecified"))
    )
    (net (code "83") (name "unconnected-(LDO1-NC-Pad4)") (class "Default")
      (node (ref "LDO1") (pin "4") (pinfunction "NC_4") (pintype "unspecified+no_connect"))
    )
    (net (code "84") (name "unconnected-(U2-PA1-Pad11)") (class "Default")
      (node (ref "U2") (pin "11") (pinfunction "PA1_11") (pintype "unspecified+no_connect"))
    )
    (net (code "85") (name "unconnected-(U2-PA4-Pad14)") (class "Default")
      (node (ref "U2") (pin "14") (pinfunction "PA4_14") (pintype "unspecified+no_connect"))
    )
    (net (code "86") (name "unconnected-(U2-PA6-Pad16)") (class "Default")
      (node (ref "U2") (pin "16") (pinfunction "PA6_16") (pintype "unspecified+no_connect"))
    )
    (net (code "87") (name "unconnected-(U2-PA7-Pad17)") (class "Default")
      (node (ref "U2") (pin "17") (pinfunction "PA7_17") (pintype "unspecified+no_connect"))
    )
    (net (code "88") (name "unconnected-(U2-PA8-Pad29)") (class "Default")
      (node (ref "U2") (pin "29") (pinfunction "PA8_29") (pintype "unspecified+no_connect"))
    )
    (net (code "89") (name "unconnected-(U2-PA10-Pad31)") (class "Default")
      (node (ref "U2") (pin "31") (pinfunction "PA10_31") (pintype "unspecified+no_connect"))
    )
    (net (code "90") (name "unconnected-(U2-PB1-Pad19)") (class "Default")
      (node (ref "U2") (pin "19") (pinfunction "PB1_19") (pintype "unspecified+no_connect"))
    )
    (net (code "91") (name "unconnected-(U2-PB4-Pad40)") (class "Default")
      (node (ref "U2") (pin "40") (pinfunction "PB4_40") (pintype "unspecified+no_connect"))
    )
    (net (code "92") (name "unconnected-(U2-PB5-Pad41)") (class "Default")
      (node (ref "U2") (pin "41") (pinfunction "PB5_41") (pintype "unspecified+no_connect"))
    )
    (net (code "93") (name "unconnected-(U2-PB6-Pad42)") (class "Default")
      (node (ref "U2") (pin "42") (pinfunction "PB6_42") (pintype "unspecified+no_connect"))
    )
    (net (code "94") (name "unconnected-(U2-PB7-Pad43)") (class "Default")
      (node (ref "U2") (pin "43") (pinfunction "PB7_43") (pintype "unspecified+no_connect"))
    )
    (net (code "95") (name "unconnected-(U2-PB8-Pad45)") (class "Default")
      (node (ref "U2") (pin "45") (pinfunction "PB8_45") (pintype "unspecified+no_connect"))
    )
    (net (code "96") (name "unconnected-(U2-PB9-Pad46)") (class "Default")
      (node (ref "U2") (pin "46") (pinfunction "PB9_46") (pintype "unspecified+no_connect"))
    )
    (net (code "97") (name "unconnected-(U2-PB10-Pad21)") (class "Default")
      (node (ref "U2") (pin "21") (pinfunction "PB10_21") (pintype "unspecified+no_connect"))
    )
    (net (code "98") (name "unconnected-(U2-PB11-Pad22)") (class "Default")
      (node (ref "U2") (pin "22") (pinfunction "PB11_22") (pintype "unspecified+no_connect"))
    )
    (net (code "99") (name "unconnected-(U2-PB15-Pad28)") (class "Default")
      (node (ref "U2") (pin "28") (pinfunction "PB15_28") (pintype "unspecified+no_connect"))
    )
    (net (code "100") (name "unconnected-(U2-PC15-OSC32_OUT-Pad4)") (class "Default")
      (node (ref "U2") (pin "4") (pinfunction "PC15-OSC32_OUT_4") (pintype "unspecified+no_connect"))
    )
    (net (code "101") (name "unconnected-(U5-VOUT-Pad2)") (class "Default")
      (node (ref "U5") (pin "2") (pinfunction "VOUT_2") (pintype "unspecified+no_connect"))
    )
    (net (code "102") (name "unconnected-(U6-PC13-TAMPER-RTC-Pad2)") (class "Default")
      (node (ref "U6") (pin "2") (pinfunction "PC13-TAMPER-RTC_2") (pintype "unspecified+no_connect"))
    )
    (net (code "103") (name "unconnected-(U6-PC14-OSC32_IN-Pad3)") (class "Default")
      (node (ref "U6") (pin "3") (pinfunction "PC14-OSC32_IN_3") (pintype "unspecified+no_connect"))
    )
    (net (code "104") (name "unconnected-(U6-PC15-OSC32_OUT-Pad4)") (class "Default")
      (node (ref "U6") (pin "4") (pinfunction "PC15-OSC32_OUT_4") (pintype "unspecified+no_connect"))
    )
    (net (code "105") (name "unconnected-(USB1-CC1-PadA5)") (class "Default")
      (node (ref "USB1") (pin "A5") (pinfunction "CC1_A5") (pintype "unspecified+no_connect"))
    )
    (net (code "106") (name "unconnected-(USB1-CC2-PadB5)") (class "Default")
      (node (ref "USB1") (pin "B5") (pinfunction "CC2_B5") (pintype "unspecified+no_connect"))
    )
    (net (code "107") (name "unconnected-(USB1-SUB1-PadA8)") (class "Default")
      (node (ref "USB1") (pin "A8") (pinfunction "SUB1_A8") (pintype "unspecified+no_connect"))
    )
    (net (code "108") (name "unconnected-(USB1-SUB2-PadB8)") (class "Default")
      (node (ref "USB1") (pin "B8") (pinfunction "SUB2_B8") (pintype "unspecified+no_connect"))
    )
  )
)
